# Tracksoar_v2.net
KiCad netlist of a schematic drawn in EAGLE
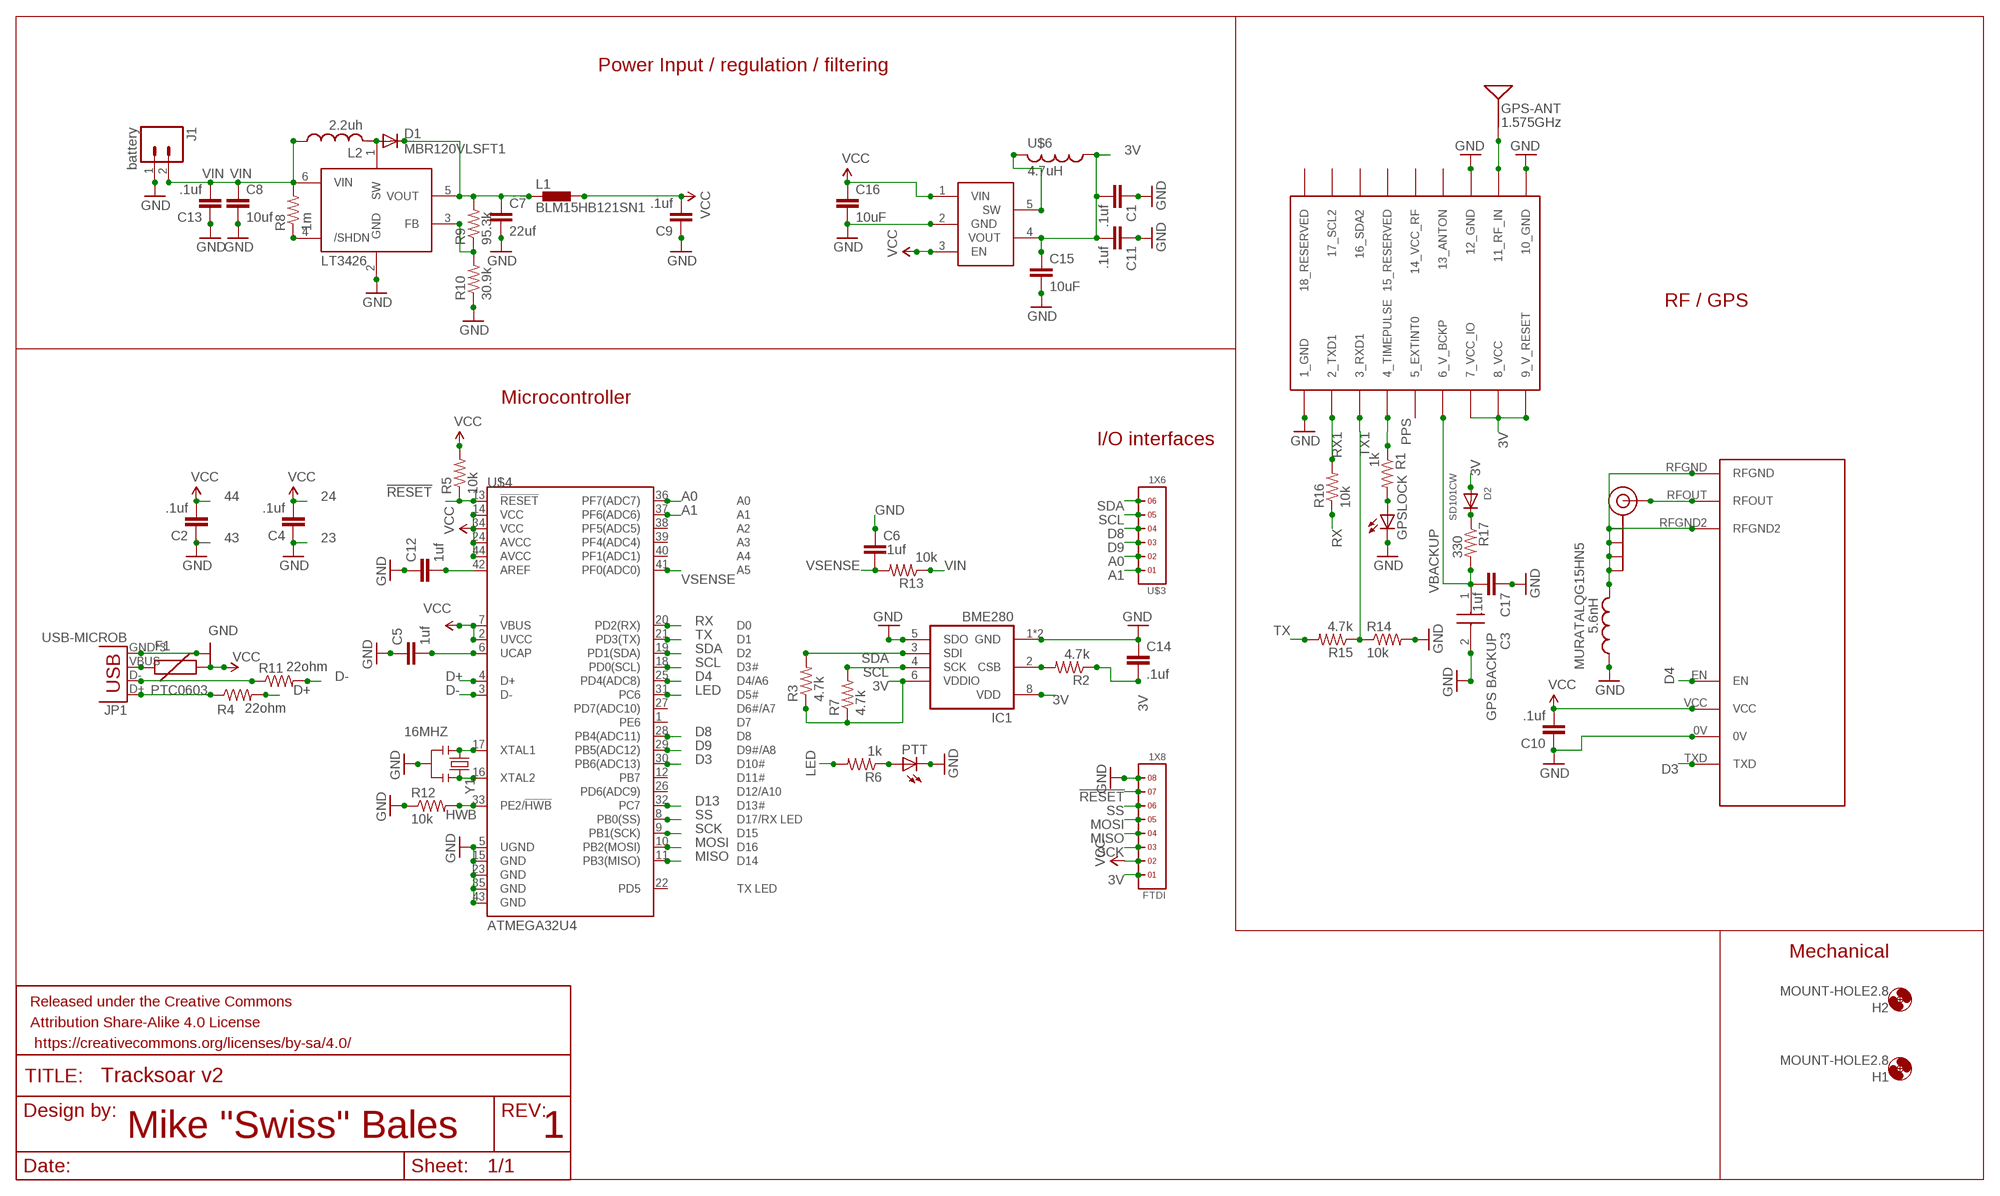
[diagram p0: schematic, sheet 1]

(export (version "E")
  (design (tool "Eeschema 10.0.6"))
  (components
    (comp (ref "C1")
      (value ".1uf")
      (footprint "eagle-import:0402-CAP")
      (libsource (lib "eagle-import") (part "CAP0402-CAP"))
    )
    (comp (ref "C2")
      (value ".1uf")
      (footprint "eagle-import:0402-CAP")
      (libsource (lib "eagle-import") (part "CAP0402-CAP"))
    )
    (comp (ref "C3")
      (value "GPS BACKUP")
      (footprint "eagle-import:DSK-3R3H204T614-H2L")
      (fields (field (name "ARROW_PART_NUMBER") "DSK-3R3H204T614-H2L"))
      (libsource (lib "eagle-import") (part "DSK-3R3H204T614-H2L"))
    )
    (comp (ref "C4")
      (value ".1uf")
      (footprint "eagle-import:0402-CAP")
      (libsource (lib "eagle-import") (part "CAP0402-CAP"))
    )
    (comp (ref "C5")
      (value "1uf")
      (footprint "eagle-import:0402-CAP")
      (libsource (lib "eagle-import") (part "CAP0402-CAP"))
    )
    (comp (ref "C6")
      (value ".1uf")
      (footprint "eagle-import:0402-CAP")
      (libsource (lib "eagle-import") (part "SparkFun-Passives_CAP0402-CAP"))
    )
    (comp (ref "C7")
      (value "22uf")
      (footprint "eagle-import:0805")
      (libsource (lib "eagle-import") (part "CAP0805"))
    )
    (comp (ref "C8")
      (value "10uf")
      (footprint "eagle-import:0805")
      (libsource (lib "eagle-import") (part "CAP0805"))
    )
    (comp (ref "C9")
      (value ".1uf")
      (footprint "eagle-import:0402-CAP")
      (libsource (lib "eagle-import") (part "CAP0402-CAP"))
    )
    (comp (ref "C10")
      (value ".1uf")
      (footprint "eagle-import:0402-CAP")
      (libsource (lib "eagle-import") (part "CAP0402-CAP"))
    )
    (comp (ref "C11")
      (value ".1uf")
      (footprint "eagle-import:0402-CAP")
      (libsource (lib "eagle-import") (part "CAP0402-CAP"))
    )
    (comp (ref "C12")
      (value "1uf")
      (footprint "eagle-import:0402-CAP")
      (libsource (lib "eagle-import") (part "CAP0402-CAP"))
    )
    (comp (ref "C13")
      (value ".1uf")
      (footprint "eagle-import:0402-CAP")
      (libsource (lib "eagle-import") (part "CAP0402-CAP"))
    )
    (comp (ref "C14")
      (value ".1uf")
      (footprint "eagle-import:0402-CAP")
      (libsource (lib "eagle-import") (part "CAP0402-CAP"))
    )
    (comp (ref "C15")
      (value "10uF")
      (footprint "eagle-import:0603")
      (libsource (lib "eagle-import") (part "10UF-0603-6.3V-20%"))
    )
    (comp (ref "C16")
      (value "10uF")
      (footprint "eagle-import:0603")
      (libsource (lib "eagle-import") (part "10UF-0603-6.3V-20%"))
    )
    (comp (ref "C17")
      (value ".1uf")
      (footprint "eagle-import:0402-CAP")
      (libsource (lib "eagle-import") (part "CAP0402-CAP"))
    )
    (comp (ref "D1")
      (value "MBR120VLSFT1")
      (footprint "eagle-import:SOD123")
      (libsource (lib "eagle-import") (part "DIODE-SOD123"))
    )
    (comp (ref "D2")
      (value "SD101CW")
      (footprint "eagle-import:SOD-123")
      (libsource (lib "eagle-import") (part "DIODESOD-123"))
    )
    (comp (ref "F1")
      (value "PTC0603")
      (footprint "eagle-import:0603")
      (libsource (lib "eagle-import") (part "PTC0603"))
    )
    (comp (ref "FRAME1")
      (value "FRAME-LETTER")
      (footprint "eagle-import:CREATIVE_COMMONS")
      (libsource (lib "eagle-import") (part "FRAME-LETTER"))
    )
    (comp (ref "FTDI")
      (value "1X8")
      (footprint "eagle-import:1X8")
      (libsource (lib "eagle-import") (part "1X8"))
    )
    (comp (ref "GPS-ANT")
      (value "1.575GHz")
      (footprint "eagle-import:ANT-GPS-2X7MM")
      (libsource (lib "eagle-import") (part "ANTENNAGPS-2X7MM"))
    )
    (comp (ref "GPSLOCK")
      (value "LEDCHIP-LED0603")
      (footprint "eagle-import:CHIP-LED0603")
      (libsource (lib "eagle-import") (part "LEDCHIP-LED0603"))
    )
    (comp (ref "H1")
      (value "MOUNT-HOLE2.8")
      (footprint "eagle-import:2,8")
      (libsource (lib "eagle-import") (part "MOUNT-HOLE2.8"))
    )
    (comp (ref "H2")
      (value "MOUNT-HOLE2.8")
      (footprint "eagle-import:2,8")
      (libsource (lib "eagle-import") (part "MOUNT-HOLE2.8"))
    )
    (comp (ref "IC1")
      (value "BME280")
      (footprint "eagle-import:BME280")
      (libsource (lib "eagle-import") (part "BME280"))
    )
    (comp (ref "J$1")
      (value "SMA_EDGE")
      (footprint "eagle-import:SMA-EDGE")
      (libsource (lib "eagle-import") (part "SMA_EDGE"))
    )
    (comp (ref "J1")
      (value "battery")
      (footprint "eagle-import:JST-2-PTH")
      (libsource (lib "eagle-import") (part "M02JST-PTH-2"))
    )
    (comp (ref "JP1")
      (value "USB-MICROB")
      (footprint "eagle-import:USB-MICROB")
      (libsource (lib "eagle-import") (part "USB-MICROB"))
    )
    (comp (ref "L1")
      (value "BLM15HB121SN1")
      (footprint "eagle-import:0402")
      (libsource (lib "eagle-import") (part "BLM15HB121SN1"))
    )
    (comp (ref "L2")
      (value "2.2uh")
      (footprint "eagle-import:L1812")
      (libsource (lib "eagle-import") (part "L-USL1812"))
    )
    (comp (ref "LT3426")
      (value "LT3426")
      (footprint "eagle-import:SOT23-6")
      (libsource (lib "eagle-import") (part "LT3426"))
    )
    (comp (ref "MURATALQG15HN5")
      (value "5.6nH")
      (footprint "eagle-import:RESC0402_N")
      (libsource (lib "eagle-import") (part "INDUCTOR_0402_N"))
    )
    (comp (ref "PTT")
      (value "LEDCHIP-LED0603")
      (footprint "eagle-import:CHIP-LED0603")
      (libsource (lib "eagle-import") (part "LEDCHIP-LED0603"))
    )
    (comp (ref "R1")
      (value "1k")
      (footprint "eagle-import:R0402")
      (libsource (lib "eagle-import") (part "R-US_R0402"))
    )
    (comp (ref "R2")
      (value "4.7k")
      (footprint "eagle-import:R0402")
      (libsource (lib "eagle-import") (part "R-US_R0402"))
    )
    (comp (ref "R3")
      (value "4.7k")
      (footprint "eagle-import:R0402")
      (libsource (lib "eagle-import") (part "R-US_R0402"))
    )
    (comp (ref "R4")
      (value "22ohm")
      (footprint "eagle-import:R0402")
      (libsource (lib "eagle-import") (part "R-US_R0402"))
    )
    (comp (ref "R5")
      (value "10k")
      (footprint "eagle-import:R0402")
      (libsource (lib "eagle-import") (part "R-US_R0402"))
    )
    (comp (ref "R6")
      (value "1k")
      (footprint "eagle-import:R0402")
      (libsource (lib "eagle-import") (part "R-US_R0402"))
    )
    (comp (ref "R7")
      (value "4.7k")
      (footprint "eagle-import:R0402")
      (libsource (lib "eagle-import") (part "R-US_R0402"))
    )
    (comp (ref "R8")
      (value "1m")
      (footprint "eagle-import:R0402")
      (libsource (lib "eagle-import") (part "R-US_R0402"))
    )
    (comp (ref "R9")
      (value "95.3k")
      (footprint "eagle-import:R0402")
      (libsource (lib "eagle-import") (part "R-US_R0402"))
    )
    (comp (ref "R10")
      (value "30.9k")
      (footprint "eagle-import:R0402")
      (libsource (lib "eagle-import") (part "R-US_R0402"))
    )
    (comp (ref "R11")
      (value "22ohm")
      (footprint "eagle-import:R0402")
      (libsource (lib "eagle-import") (part "R-US_R0402"))
    )
    (comp (ref "R12")
      (value "10k")
      (footprint "eagle-import:R0402")
      (libsource (lib "eagle-import") (part "R-US_R0402"))
    )
    (comp (ref "R13")
      (value "10k")
      (footprint "eagle-import:R0402")
      (libsource (lib "eagle-import") (part "R-US_R0402"))
    )
    (comp (ref "R14")
      (value "10k")
      (footprint "eagle-import:R0402")
      (libsource (lib "eagle-import") (part "R-US_R0402"))
    )
    (comp (ref "R15")
      (value "4.7k")
      (footprint "eagle-import:R0402")
      (libsource (lib "eagle-import") (part "R-US_R0402"))
    )
    (comp (ref "R16")
      (value "10k")
      (footprint "eagle-import:R0402")
      (libsource (lib "eagle-import") (part "R-US_R0402"))
    )
    (comp (ref "R17")
      (value "330")
      (footprint "eagle-import:R0402")
      (libsource (lib "eagle-import") (part "R-US_R0402"))
    )
    (comp (ref "U$1")
      (value "UBLOX_MAX")
      (footprint "eagle-import:UBLOX_MAX")
      (libsource (lib "eagle-import") (part "UBLOX_MAX"))
    )
    (comp (ref "U$2")
      (value "RADIOMETRIX-HX1")
      (footprint "eagle-import:RADIOMETRIX-HX1")
      (libsource (lib "eagle-import") (part "RADIOMETRIX-HX1"))
    )
    (comp (ref "U$3")
      (value "1X6")
      (footprint "eagle-import:1X6")
      (libsource (lib "eagle-import") (part "1X6"))
    )
    (comp (ref "U$4")
      (value "ATMEGA32U4")
      (footprint "eagle-import:QFN-44-NOPAD")
      (libsource (lib "eagle-import") (part "ATMEGA32U4QFN2"))
    )
    (comp (ref "U$5")
      (value "PAM2305")
      (footprint "eagle-import:DBV_R-PDSO-G5")
      (libsource (lib "eagle-import") (part "PAM2305-33SOT23-5"))
    )
    (comp (ref "U$6")
      (value "4.7uH")
      (footprint "eagle-import:RESC0805_N")
      (libsource (lib "eagle-import") (part "INDUCTOR_0805_N"))
    )
    (comp (ref "Y1")
      (value "16MHZ")
      (footprint "eagle-import:RESONATOR-SMD")
      (libsource (lib "eagle-import") (part "RESONATOR16MHZ"))
    )
  )
  (nets
    (net (code "1") (name "/3V") (class "Default")
      (node (ref "C1") (pin "2") (pinfunction "2_2") (pintype "passive"))
      (node (ref "C11") (pin "2") (pinfunction "2_2") (pintype "passive"))
      (node (ref "C14") (pin "2") (pinfunction "2_2") (pintype "passive"))
      (node (ref "C15") (pin "1") (pinfunction "1_1") (pintype "passive"))
      (node (ref "D2") (pin "A") (pinfunction "A_A") (pintype "passive"))
      (node (ref "FTDI") (pin "1") (pinfunction "1_1") (pintype "bidirectional"))
      (node (ref "IC1") (pin "6") (pinfunction "VDDIO_6") (pintype "power_in"))
      (node (ref "IC1") (pin "8") (pinfunction "VDD_8") (pintype "power_in"))
      (node (ref "R2") (pin "1") (pinfunction "1_1") (pintype "passive"))
      (node (ref "R3") (pin "1") (pinfunction "1_1") (pintype "passive"))
      (node (ref "R7") (pin "1") (pinfunction "1_1") (pintype "passive"))
      (node (ref "U$1") (pin "7_VCC_IO") (pinfunction "7_VCC_IO_7_VCC_IO") (pintype "power_in"))
      (node (ref "U$1") (pin "8_VCC") (pinfunction "8_VCC_8_VCC") (pintype "power_in"))
      (node (ref "U$1") (pin "9_V_RESET") (pinfunction "9_V_RESET_9_V_RESET") (pintype "power_in"))
      (node (ref "U$5") (pin "4") (pinfunction "VOUT_4") (pintype "bidirectional"))
      (node (ref "U$6") (pin "1") (pinfunction "1_1") (pintype "passive"))
    )
    (net (code "2") (name "/A0") (class "Default")
      (node (ref "U$3") (pin "2") (pinfunction "2_2") (pintype "bidirectional"))
      (node (ref "U$4") (pin "36") (pinfunction "PF7(ADC7)_36") (pintype "bidirectional"))
    )
    (net (code "3") (name "/A1") (class "Default")
      (node (ref "U$3") (pin "1") (pinfunction "1_1") (pintype "bidirectional"))
      (node (ref "U$4") (pin "37") (pinfunction "PF6(ADC6)_37") (pintype "bidirectional"))
    )
    (net (code "4") (name "/D+") (class "Default")
      (node (ref "R4") (pin "2") (pinfunction "2_2") (pintype "passive"))
      (node (ref "U$4") (pin "4") (pinfunction "D+_4") (pintype "bidirectional"))
    )
    (net (code "5") (name "/D-") (class "Default")
      (node (ref "R11") (pin "2") (pinfunction "2_2") (pintype "passive"))
      (node (ref "U$4") (pin "3") (pinfunction "D-_3") (pintype "bidirectional"))
    )
    (net (code "6") (name "/D3") (class "Default")
      (node (ref "U$2") (pin "TXD") (pinfunction "TXD_TXD") (pintype "bidirectional"))
      (node (ref "U$4") (pin "30") (pinfunction "PB6(ADC13)_30") (pintype "bidirectional"))
    )
    (net (code "7") (name "/D4") (class "Default")
      (node (ref "U$2") (pin "EN") (pinfunction "EN_EN") (pintype "bidirectional"))
      (node (ref "U$4") (pin "25") (pinfunction "PD4(ADC8)_25") (pintype "bidirectional"))
    )
    (net (code "8") (name "/D8") (class "Default")
      (node (ref "U$3") (pin "4") (pinfunction "4_4") (pintype "bidirectional"))
      (node (ref "U$4") (pin "28") (pinfunction "PB4(ADC11)_28") (pintype "bidirectional"))
    )
    (net (code "9") (name "/D9") (class "Default")
      (node (ref "U$3") (pin "3") (pinfunction "3_3") (pintype "bidirectional"))
      (node (ref "U$4") (pin "29") (pinfunction "PB5(ADC12)_29") (pintype "bidirectional"))
    )
    (net (code "10") (name "/D13") (class "Default")
      (node (ref "U$4") (pin "32") (pinfunction "PC7_32") (pintype "bidirectional"))
    )
    (net (code "11") (name "/HWB") (class "Default")
      (node (ref "R12") (pin "2") (pinfunction "2_2") (pintype "passive"))
      (node (ref "U$4") (pin "33") (pinfunction "PE2/~{HWB}_33") (pintype "bidirectional"))
    )
    (net (code "12") (name "/LED") (class "Default")
      (node (ref "R6") (pin "2") (pinfunction "2_2") (pintype "passive"))
      (node (ref "U$4") (pin "31") (pinfunction "PC6_31") (pintype "bidirectional"))
    )
    (net (code "13") (name "/MISO") (class "Default")
      (node (ref "FTDI") (pin "4") (pinfunction "4_4") (pintype "bidirectional"))
      (node (ref "U$4") (pin "11") (pinfunction "PB3(MISO)_11") (pintype "bidirectional"))
    )
    (net (code "14") (name "/MOSI") (class "Default")
      (node (ref "FTDI") (pin "5") (pinfunction "5_5") (pintype "bidirectional"))
      (node (ref "U$4") (pin "10") (pinfunction "PB2(MOSI)_10") (pintype "bidirectional"))
    )
    (net (code "15") (name "/PPS") (class "Default")
      (node (ref "R1") (pin "1") (pinfunction "1_1") (pintype "passive"))
      (node (ref "U$1") (pin "4_TIMEPULSE") (pinfunction "4_TIMEPULSE_4_TIMEPULSE") (pintype "bidirectional"))
    )
    (net (code "16") (name "/RFGND") (class "Default")
      (node (ref "J$1") (pin "GND@0") (pinfunction "GND_GND@0") (pintype "bidirectional"))
      (node (ref "J$1") (pin "GND@1") (pinfunction "GND_GND@1") (pintype "bidirectional"))
      (node (ref "J$1") (pin "GND@2") (pinfunction "GND_GND@2") (pintype "bidirectional"))
      (node (ref "J$1") (pin "GND@3") (pinfunction "GND_GND@3") (pintype "bidirectional"))
      (node (ref "MURATALQG15HN5") (pin "2") (pinfunction "2_2") (pintype "passive"))
      (node (ref "U$2") (pin "RFGND") (pinfunction "RFGND_RFGND") (pintype "bidirectional"))
      (node (ref "U$2") (pin "RFGND2") (pinfunction "RFGND2_RFGND2") (pintype "bidirectional"))
    )
    (net (code "17") (name "/RX") (class "Default")
      (node (ref "R16") (pin "1") (pinfunction "1_1") (pintype "passive"))
      (node (ref "U$4") (pin "20") (pinfunction "PD2(RX)_20") (pintype "bidirectional"))
    )
    (net (code "18") (name "/RX1") (class "Default")
      (node (ref "R16") (pin "2") (pinfunction "2_2") (pintype "passive"))
      (node (ref "U$1") (pin "2_TXD1") (pinfunction "2_TXD1_2_TXD1") (pintype "bidirectional"))
    )
    (net (code "19") (name "/SCK") (class "Default")
      (node (ref "FTDI") (pin "3") (pinfunction "3_3") (pintype "bidirectional"))
      (node (ref "U$4") (pin "9") (pinfunction "PB1(SCK)_9") (pintype "bidirectional"))
    )
    (net (code "20") (name "/SCL") (class "Default")
      (node (ref "IC1") (pin "4") (pinfunction "SCK_4") (pintype "bidirectional"))
      (node (ref "R7") (pin "2") (pinfunction "2_2") (pintype "passive"))
      (node (ref "U$3") (pin "5") (pinfunction "5_5") (pintype "bidirectional"))
      (node (ref "U$4") (pin "18") (pinfunction "PD0(SCL)_18") (pintype "bidirectional"))
    )
    (net (code "21") (name "/SDA") (class "Default")
      (node (ref "IC1") (pin "3") (pinfunction "SDI_3") (pintype "bidirectional"))
      (node (ref "R3") (pin "2") (pinfunction "2_2") (pintype "passive"))
      (node (ref "U$3") (pin "6") (pinfunction "6_6") (pintype "bidirectional"))
      (node (ref "U$4") (pin "19") (pinfunction "PD1(SDA)_19") (pintype "bidirectional"))
    )
    (net (code "22") (name "/SS") (class "Default")
      (node (ref "FTDI") (pin "6") (pinfunction "6_6") (pintype "bidirectional"))
      (node (ref "U$4") (pin "8") (pinfunction "PB0(SS)_8") (pintype "bidirectional"))
    )
    (net (code "23") (name "/TX") (class "Default")
      (node (ref "R15") (pin "2") (pinfunction "2_2") (pintype "passive"))
      (node (ref "U$4") (pin "21") (pinfunction "PD3(TX)_21") (pintype "bidirectional"))
    )
    (net (code "24") (name "/TX1") (class "Default")
      (node (ref "R14") (pin "1") (pinfunction "1_1") (pintype "passive"))
      (node (ref "R15") (pin "1") (pinfunction "1_1") (pintype "passive"))
      (node (ref "U$1") (pin "3_RXD1") (pinfunction "3_RXD1_3_RXD1") (pintype "bidirectional"))
    )
    (net (code "25") (name "/VBACKUP") (class "Default")
      (node (ref "C17") (pin "2") (pinfunction "2_2") (pintype "passive"))
      (node (ref "C3") (pin "1") (pinfunction "+_1") (pintype "bidirectional"))
      (node (ref "R17") (pin "2") (pinfunction "2_2") (pintype "passive"))
      (node (ref "U$1") (pin "6_V_BCKP") (pinfunction "6_V_BCKP_6_V_BCKP") (pintype "bidirectional"))
    )
    (net (code "26") (name "/VIN") (class "Default")
      (node (ref "C13") (pin "2") (pinfunction "2_2") (pintype "passive"))
      (node (ref "C8") (pin "1") (pinfunction "1_1") (pintype "passive"))
      (node (ref "J1") (pin "2") (pinfunction "2_2") (pintype "passive"))
      (node (ref "L2") (pin "1") (pinfunction "1_1") (pintype "passive"))
      (node (ref "LT3426") (pin "6") (pinfunction "VIN_6") (pintype "input"))
      (node (ref "R13") (pin "1") (pinfunction "1_1") (pintype "passive"))
      (node (ref "R8") (pin "2") (pinfunction "2_2") (pintype "passive"))
    )
    (net (code "27") (name "/VSENSE") (class "Default")
      (node (ref "C6") (pin "2") (pinfunction "2_2") (pintype "passive"))
      (node (ref "R13") (pin "2") (pinfunction "2_2") (pintype "passive"))
      (node (ref "U$4") (pin "41") (pinfunction "PF0(ADC0)_41") (pintype "bidirectional"))
    )
    (net (code "28") (name "/~{RESET}") (class "Default")
      (node (ref "FTDI") (pin "7") (pinfunction "7_7") (pintype "bidirectional"))
      (node (ref "R5") (pin "1") (pinfunction "1_1") (pintype "passive"))
      (node (ref "U$4") (pin "13") (pinfunction "~{RESET}_13") (pintype "bidirectional"))
    )
    (net (code "29") (name "GND") (class "Default")
      (node (ref "C1") (pin "1") (pinfunction "1_1") (pintype "passive"))
      (node (ref "C10") (pin "1") (pinfunction "1_1") (pintype "passive"))
      (node (ref "C11") (pin "1") (pinfunction "1_1") (pintype "passive"))
      (node (ref "C12") (pin "1") (pinfunction "1_1") (pintype "passive"))
      (node (ref "C13") (pin "1") (pinfunction "1_1") (pintype "passive"))
      (node (ref "C14") (pin "1") (pinfunction "1_1") (pintype "passive"))
      (node (ref "C15") (pin "2") (pinfunction "2_2") (pintype "passive"))
      (node (ref "C16") (pin "2") (pinfunction "2_2") (pintype "passive"))
      (node (ref "C17") (pin "1") (pinfunction "1_1") (pintype "passive"))
      (node (ref "C2") (pin "1") (pinfunction "1_1") (pintype "passive"))
      (node (ref "C3") (pin "2") (pinfunction "-_2") (pintype "bidirectional"))
      (node (ref "C4") (pin "1") (pinfunction "1_1") (pintype "passive"))
      (node (ref "C5") (pin "1") (pinfunction "1_1") (pintype "passive"))
      (node (ref "C6") (pin "1") (pinfunction "1_1") (pintype "passive"))
      (node (ref "C7") (pin "2") (pinfunction "2_2") (pintype "passive"))
      (node (ref "C8") (pin "2") (pinfunction "2_2") (pintype "passive"))
      (node (ref "C9") (pin "1") (pinfunction "1_1") (pintype "passive"))
      (node (ref "FTDI") (pin "8") (pinfunction "8_8") (pintype "bidirectional"))
      (node (ref "GPSLOCK") (pin "C") (pinfunction "C_C") (pintype "passive"))
      (node (ref "IC1") (pin "1") (pinfunction "GND_1") (pintype "power_in"))
      (node (ref "IC1") (pin "5") (pinfunction "SDO_5") (pintype "input"))
      (node (ref "IC1") (pin "7") (pinfunction "GND_7") (pintype "power_in"))
      (node (ref "J1") (pin "1") (pinfunction "1_1") (pintype "passive"))
      (node (ref "JP1") (pin "GND") (pinfunction "GND_GND") (pintype "bidirectional"))
      (node (ref "JP1") (pin "MT1") (pinfunction "GND_MT1") (pintype "bidirectional"))
      (node (ref "JP1") (pin "MT2") (pinfunction "GND_MT2") (pintype "bidirectional"))
      (node (ref "LT3426") (pin "2") (pinfunction "GND_2") (pintype "power_in"))
      (node (ref "MURATALQG15HN5") (pin "1") (pinfunction "1_1") (pintype "passive"))
      (node (ref "PTT") (pin "C") (pinfunction "C_C") (pintype "passive"))
      (node (ref "R10") (pin "1") (pinfunction "1_1") (pintype "passive"))
      (node (ref "R12") (pin "1") (pinfunction "1_1") (pintype "passive"))
      (node (ref "R14") (pin "2") (pinfunction "2_2") (pintype "passive"))
      (node (ref "U$1") (pin "10_GND") (pinfunction "10_GND_10_GND") (pintype "power_in"))
      (node (ref "U$1") (pin "12_GND") (pinfunction "12_GND_12_GND") (pintype "power_in"))
      (node (ref "U$1") (pin "1_GND") (pinfunction "1_GND_1_GND") (pintype "power_in"))
      (node (ref "U$2") (pin "0V") (pinfunction "0V_0V") (pintype "bidirectional"))
      (node (ref "U$4") (pin "15") (pinfunction "GND_15") (pintype "bidirectional"))
      (node (ref "U$4") (pin "23") (pinfunction "GND_23") (pintype "bidirectional"))
      (node (ref "U$4") (pin "35") (pinfunction "GND_35") (pintype "bidirectional"))
      (node (ref "U$4") (pin "43") (pinfunction "GND_43") (pintype "bidirectional"))
      (node (ref "U$4") (pin "5") (pinfunction "UGND_5") (pintype "bidirectional"))
      (node (ref "U$5") (pin "2") (pinfunction "GND_2") (pintype "bidirectional"))
      (node (ref "Y1") (pin "2") (pinfunction "2_2") (pintype "passive"))
    )
    (net (code "30") (name "Net-(D2-PadC)") (class "Default")
      (node (ref "D2") (pin "C") (pinfunction "C_C") (pintype "passive"))
      (node (ref "R17") (pin "1") (pinfunction "1_1") (pintype "passive"))
    )
    (net (code "31") (name "Net-(F1-Pad1)") (class "Default")
      (node (ref "F1") (pin "1") (pinfunction "1_1") (pintype "bidirectional"))
      (node (ref "JP1") (pin "VBUS") (pinfunction "VBUS_VBUS") (pintype "bidirectional"))
    )
    (net (code "32") (name "Net-(GPS-ANT-SIGNAL)") (class "Default")
      (node (ref "GPS-ANT") (pin "1") (pinfunction "SIGNAL_1") (pintype "bidirectional"))
      (node (ref "U$1") (pin "11_RF_IN") (pinfunction "11_RF_IN_11_RF_IN") (pintype "bidirectional"))
    )
    (net (code "33") (name "Net-(GPSLOCK-PadA)") (class "Default")
      (node (ref "GPSLOCK") (pin "A") (pinfunction "A_A") (pintype "passive"))
      (node (ref "R1") (pin "2") (pinfunction "2_2") (pintype "passive"))
    )
    (net (code "34") (name "Net-(IC1-CSB)") (class "Default")
      (node (ref "IC1") (pin "2") (pinfunction "CSB_2") (pintype "input"))
      (node (ref "R2") (pin "2") (pinfunction "2_2") (pintype "passive"))
    )
    (net (code "35") (name "Net-(J$1-SIGNAL)") (class "Default")
      (node (ref "J$1") (pin "SIG") (pinfunction "SIGNAL_SIG") (pintype "bidirectional"))
      (node (ref "U$2") (pin "RFOUT") (pinfunction "RFOUT_RFOUT") (pintype "bidirectional"))
    )
    (net (code "36") (name "Net-(JP1-PadD+)") (class "Default")
      (node (ref "JP1") (pin "D+") (pinfunction "D+_D+") (pintype "bidirectional"))
      (node (ref "R4") (pin "1") (pinfunction "1_1") (pintype "passive"))
    )
    (net (code "37") (name "Net-(JP1-PadD-)") (class "Default")
      (node (ref "JP1") (pin "D-") (pinfunction "D-_D-") (pintype "bidirectional"))
      (node (ref "R11") (pin "1") (pinfunction "1_1") (pintype "passive"))
    )
    (net (code "38") (name "Net-(LT3426-FB)") (class "Default")
      (node (ref "LT3426") (pin "3") (pinfunction "FB_3") (pintype "input"))
      (node (ref "R10") (pin "2") (pinfunction "2_2") (pintype "passive"))
      (node (ref "R9") (pin "1") (pinfunction "1_1") (pintype "passive"))
    )
    (net (code "39") (name "Net-(LT3426-SW)") (class "Default")
      (node (ref "D1") (pin "A") (pinfunction "A_A") (pintype "passive"))
      (node (ref "L2") (pin "2") (pinfunction "2_2") (pintype "passive"))
      (node (ref "LT3426") (pin "1") (pinfunction "SW_1") (pintype "output"))
    )
    (net (code "40") (name "Net-(LT3426-VOUT)") (class "Default")
      (node (ref "C7") (pin "1") (pinfunction "1_1") (pintype "passive"))
      (node (ref "D1") (pin "C") (pinfunction "C_C") (pintype "passive"))
      (node (ref "L1") (pin "1") (pinfunction "1_1") (pintype "passive"))
      (node (ref "LT3426") (pin "5") (pinfunction "VOUT_5") (pintype "output"))
      (node (ref "R9") (pin "2") (pinfunction "2_2") (pintype "passive"))
    )
    (net (code "41") (name "Net-(LT3426-{slash}SHDN)") (class "Default")
      (node (ref "LT3426") (pin "4") (pinfunction "/SHDN_4") (pintype "input"))
      (node (ref "R8") (pin "1") (pinfunction "1_1") (pintype "passive"))
    )
    (net (code "42") (name "Net-(PTT-PadA)") (class "Default")
      (node (ref "PTT") (pin "A") (pinfunction "A_A") (pintype "passive"))
      (node (ref "R6") (pin "1") (pinfunction "1_1") (pintype "passive"))
    )
    (net (code "43") (name "Net-(U$4-AREF)") (class "Default")
      (node (ref "C12") (pin "2") (pinfunction "2_2") (pintype "passive"))
      (node (ref "U$4") (pin "42") (pinfunction "AREF_42") (pintype "bidirectional"))
    )
    (net (code "44") (name "Net-(U$4-UCAP)") (class "Default")
      (node (ref "C5") (pin "2") (pinfunction "2_2") (pintype "passive"))
      (node (ref "U$4") (pin "6") (pinfunction "UCAP_6") (pintype "bidirectional"))
    )
    (net (code "45") (name "Net-(U$4-XTAL1)") (class "Default")
      (node (ref "U$4") (pin "17") (pinfunction "XTAL1_17") (pintype "bidirectional"))
      (node (ref "Y1") (pin "1") (pinfunction "1_1") (pintype "passive"))
    )
    (net (code "46") (name "Net-(U$4-XTAL2)") (class "Default")
      (node (ref "U$4") (pin "16") (pinfunction "XTAL2_16") (pintype "bidirectional"))
      (node (ref "Y1") (pin "3") (pinfunction "3_3") (pintype "passive"))
    )
    (net (code "47") (name "Net-(U$5-SW)") (class "Default")
      (node (ref "U$5") (pin "5") (pinfunction "SW_5") (pintype "bidirectional"))
      (node (ref "U$6") (pin "2") (pinfunction "2_2") (pintype "passive"))
    )
    (net (code "48") (name "VCC") (class "Default")
      (node (ref "C10") (pin "2") (pinfunction "2_2") (pintype "passive"))
      (node (ref "C16") (pin "1") (pinfunction "1_1") (pintype "passive"))
      (node (ref "C2") (pin "2") (pinfunction "2_2") (pintype "passive"))
      (node (ref "C4") (pin "2") (pinfunction "2_2") (pintype "passive"))
      (node (ref "C9") (pin "2") (pinfunction "2_2") (pintype "passive"))
      (node (ref "F1") (pin "2") (pinfunction "2_2") (pintype "bidirectional"))
      (node (ref "FTDI") (pin "2") (pinfunction "2_2") (pintype "bidirectional"))
      (node (ref "L1") (pin "2") (pinfunction "2_2") (pintype "passive"))
      (node (ref "R5") (pin "2") (pinfunction "2_2") (pintype "passive"))
      (node (ref "U$2") (pin "VCC") (pinfunction "VCC_VCC") (pintype "bidirectional"))
      (node (ref "U$4") (pin "14") (pinfunction "VCC_14") (pintype "bidirectional"))
      (node (ref "U$4") (pin "2") (pinfunction "UVCC_2") (pintype "bidirectional"))
      (node (ref "U$4") (pin "24") (pinfunction "AVCC_24") (pintype "bidirectional"))
      (node (ref "U$4") (pin "34") (pinfunction "VCC_34") (pintype "bidirectional"))
      (node (ref "U$4") (pin "44") (pinfunction "AVCC_44") (pintype "bidirectional"))
      (node (ref "U$4") (pin "7") (pinfunction "VBUS_7") (pintype "bidirectional"))
      (node (ref "U$5") (pin "1") (pinfunction "VIN_1") (pintype "bidirectional"))
      (node (ref "U$5") (pin "3") (pinfunction "EN_3") (pintype "bidirectional"))
    )
    (net (code "49") (name "unconnected-(U$1-Pad5_EXTINT0)") (class "Default")
      (node (ref "U$1") (pin "5_EXTINT0") (pinfunction "5_EXTINT0_5_EXTINT0") (pintype "bidirectional"))
    )
    (net (code "50") (name "unconnected-(U$1-Pad13_ANTON)") (class "Default")
      (node (ref "U$1") (pin "13_ANTON") (pinfunction "13_ANTON_13_ANTON") (pintype "bidirectional"))
    )
    (net (code "51") (name "unconnected-(U$1-Pad14_VCC_RF)") (class "Default")
      (node (ref "U$1") (pin "14_VCC_RF") (pinfunction "14_VCC_RF_14_VCC_RF") (pintype "bidirectional"))
    )
    (net (code "52") (name "unconnected-(U$1-Pad15_RESERVED)") (class "Default")
      (node (ref "U$1") (pin "15_RESERVED") (pinfunction "15_RESERVED_15_RESERVED") (pintype "bidirectional"))
    )
    (net (code "53") (name "unconnected-(U$1-Pad16_SDA2)") (class "Default")
      (node (ref "U$1") (pin "16_SDA2") (pinfunction "16_SDA2_16_SDA2") (pintype "bidirectional"))
    )
    (net (code "54") (name "unconnected-(U$1-Pad17_SCL2)") (class "Default")
      (node (ref "U$1") (pin "17_SCL2") (pinfunction "17_SCL2_17_SCL2") (pintype "bidirectional"))
    )
    (net (code "55") (name "unconnected-(U$1-Pad18_RESERVED)") (class "Default")
      (node (ref "U$1") (pin "18_RESERVED") (pinfunction "18_RESERVED_18_RESERVED") (pintype "bidirectional"))
    )
    (net (code "56") (name "unconnected-(U$4-PB7-Pad12)") (class "Default")
      (node (ref "U$4") (pin "12") (pinfunction "PB7_12") (pintype "bidirectional"))
    )
    (net (code "57") (name "unconnected-(U$4-PD5-Pad22)") (class "Default")
      (node (ref "U$4") (pin "22") (pinfunction "PD5_22") (pintype "bidirectional"))
    )
    (net (code "58") (name "unconnected-(U$4-PD6(ADC9)-Pad26)") (class "Default")
      (node (ref "U$4") (pin "26") (pinfunction "PD6(ADC9)_26") (pintype "bidirectional"))
    )
    (net (code "59") (name "unconnected-(U$4-PD7(ADC10)-Pad27)") (class "Default")
      (node (ref "U$4") (pin "27") (pinfunction "PD7(ADC10)_27") (pintype "bidirectional"))
    )
    (net (code "60") (name "unconnected-(U$4-PE6-Pad1)") (class "Default")
      (node (ref "U$4") (pin "1") (pinfunction "PE6_1") (pintype "bidirectional"))
    )
    (net (code "61") (name "unconnected-(U$4-PF1(ADC1)-Pad40)") (class "Default")
      (node (ref "U$4") (pin "40") (pinfunction "PF1(ADC1)_40") (pintype "bidirectional"))
    )
    (net (code "62") (name "unconnected-(U$4-PF4(ADC4)-Pad39)") (class "Default")
      (node (ref "U$4") (pin "39") (pinfunction "PF4(ADC4)_39") (pintype "bidirectional"))
    )
    (net (code "63") (name "unconnected-(U$4-PF5(ADC5)-Pad38)") (class "Default")
      (node (ref "U$4") (pin "38") (pinfunction "PF5(ADC5)_38") (pintype "bidirectional"))
    )
  )
)
